# Sheet1.net
KiCad netlist of a schematic drawn in Altium Designer
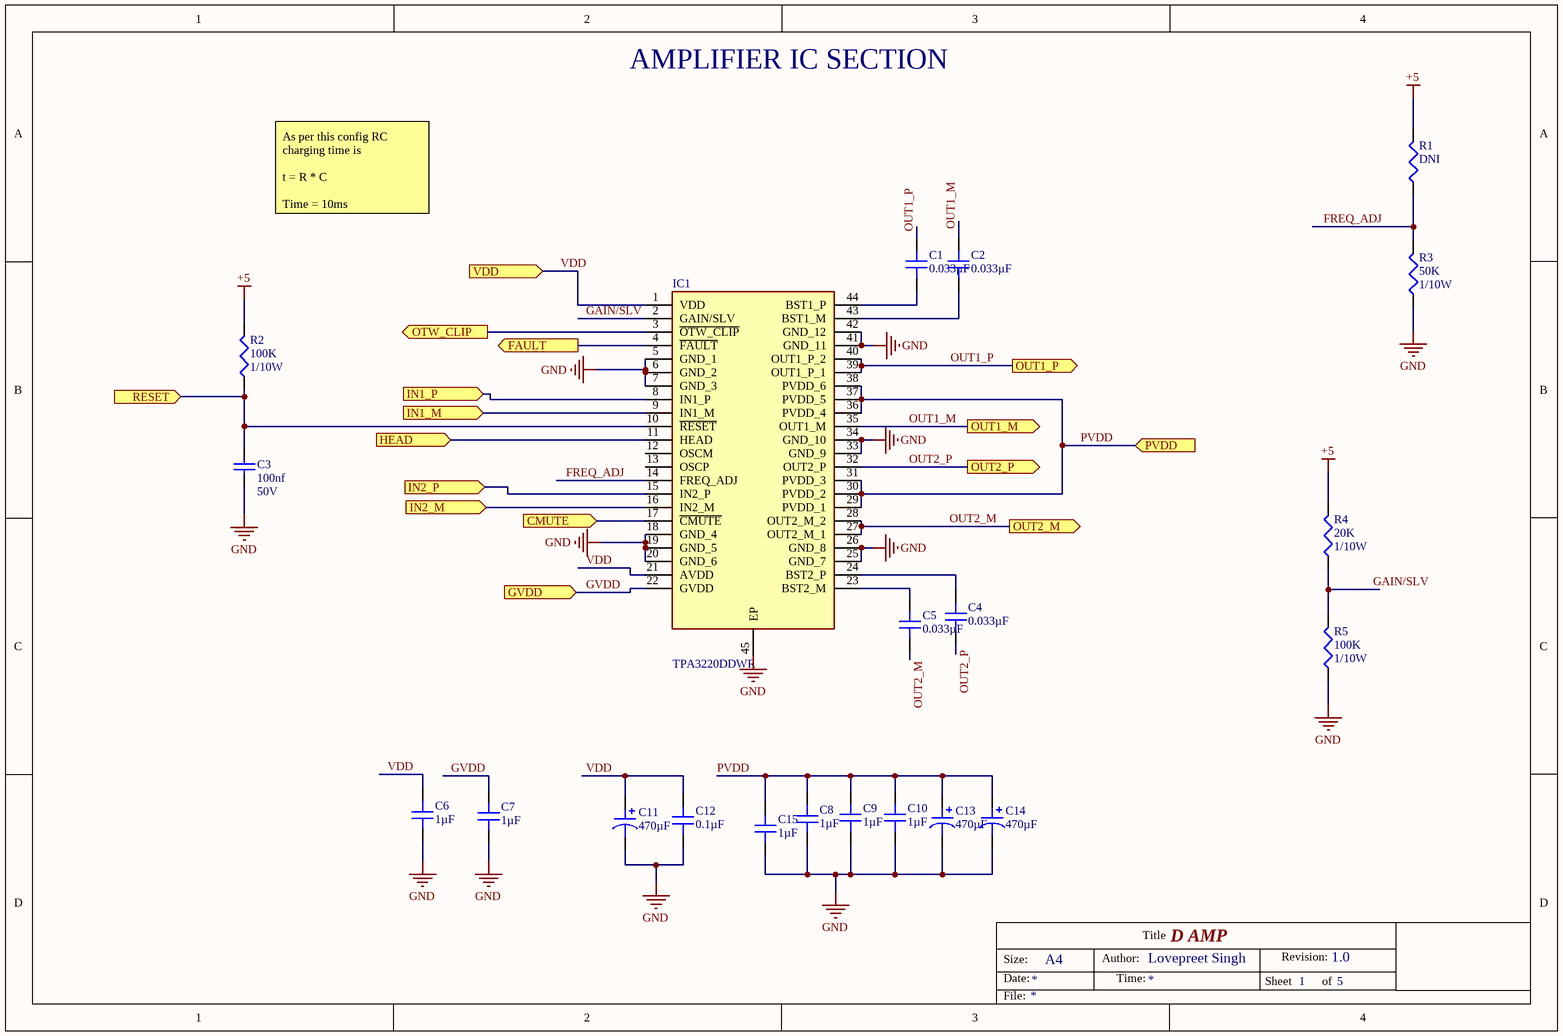
[diagram p0: Sheet1.SchDoc]

(export (version "E")
  (design (tool "Eeschema 10.0.6"))
  (components
    (comp (ref "C1")
      (value "0.033µF")
      (footprint "CAP 0603_1608")
      (description "CAP CER 0.033UF 100V X8R 0603")
      (fields
        (field (name "PART NUMBER") "C1608X8R2A333K080AB")
        (field (name "MANUFACTURER") "TDK Corporation")
      )
      (libsource (lib "Celestial Altium Library - altium_library") (part "Capacitor"))
    )
    (comp (ref "C2")
      (value "0.033µF")
      (footprint "CAP 0603_1608")
      (description "CAP CER 0.033UF 100V X8R 0603")
      (fields
        (field (name "PART NUMBER") "C1608X8R2A333K080AB")
        (field (name "MANUFACTURER") "TDK Corporation")
      )
      (libsource (lib "Celestial Altium Library - altium_library") (part "Capacitor"))
    )
    (comp (ref "C3")
      (value "100nf")
      (footprint "C0603")
      (description "CAP CER 100NF 10% 50V X7R 0603")
      (fields (field (name "VRATING") "50V"))
      (libsource (lib "Database_Libs1") (part "CAP_NPOL"))
    )
    (comp (ref "C4")
      (value "0.033µF")
      (footprint "CAP 0603_1608")
      (description "CAP CER 0.033UF 100V X8R 0603")
      (fields
        (field (name "PART NUMBER") "C1608X8R2A333K080AB")
        (field (name "MANUFACTURER") "TDK Corporation")
      )
      (libsource (lib "Celestial Altium Library - altium_library") (part "Capacitor"))
    )
    (comp (ref "C5")
      (value "0.033µF")
      (footprint "CAP 0603_1608")
      (description "CAP CER 0.033UF 100V X8R 0603")
      (fields
        (field (name "PART NUMBER") "C1608X8R2A333K080AB")
        (field (name "MANUFACTURER") "TDK Corporation")
      )
      (libsource (lib "Celestial Altium Library - altium_library") (part "Capacitor"))
    )
    (comp (ref "C6")
      (value "1µF")
      (footprint "CAP 0805_2012")
      (description "CAP CER 1UF 50V X7R 0805")
      (fields
        (field (name "PART NUMBER") "GCM21BR71H105KA03L")
        (field (name "MANUFACTURER") "Murata Electronics")
      )
      (libsource (lib "Celestial Altium Library - altium_library") (part "Capacitor"))
    )
    (comp (ref "C7")
      (value "1µF")
      (footprint "CAP 0805_2012")
      (description "CAP CER 1UF 50V X7R 0805")
      (fields
        (field (name "PART NUMBER") "GCM21BR71H105KA03L")
        (field (name "MANUFACTURER") "Murata Electronics")
      )
      (libsource (lib "Celestial Altium Library - altium_library") (part "Capacitor"))
    )
    (comp (ref "C8")
      (value "1µF")
      (footprint "CAP 0805_2012")
      (description "CAP CER 1UF 50V X7R 0805")
      (fields
        (field (name "PART NUMBER") "GCM21BR71H105KA03L")
        (field (name "MANUFACTURER") "Murata Electronics")
      )
      (libsource (lib "Celestial Altium Library - altium_library") (part "Capacitor"))
    )
    (comp (ref "C9")
      (value "1µF")
      (footprint "CAP 0805_2012")
      (description "CAP CER 1UF 50V X7R 0805")
      (fields
        (field (name "PART NUMBER") "GCM21BR71H105KA03L")
        (field (name "MANUFACTURER") "Murata Electronics")
      )
      (libsource (lib "Celestial Altium Library - altium_library") (part "Capacitor"))
    )
    (comp (ref "C10")
      (value "1µF")
      (footprint "CAP 0805_2012")
      (description "CAP CER 1UF 50V X7R 0805")
      (fields
        (field (name "PART NUMBER") "GCM21BR71H105KA03L")
        (field (name "MANUFACTURER") "Murata Electronics")
      )
      (libsource (lib "Celestial Altium Library - altium_library") (part "Capacitor"))
    )
    (comp (ref "C11")
      (value "470µF")
      (footprint "CAP TH ALUM ELEC D12.50mm S5.00mm H27.00mm")
      (description "CAP 470UF 50V RAD")
      (fields (field (name "PART NUMBER") "UBT1H471MHD") (field (name "MANUFACTURER") "Nichicon"))
      (libsource (lib "Celestial Altium Library - altium_library") (part "Polarised Capacitor"))
    )
    (comp (ref "C12")
      (value "0.1µF")
      (footprint "CAP 0805_2012")
      (description "CAP CER 0805 10% X8R 50V 100NF")
      (fields (field (name "PART NUMBER") "AC0805KKX8R9BB104") (field (name "MANUFACTURER") "Yageo"))
      (libsource (lib "Celestial Altium Library - altium_library") (part "Capacitor"))
    )
    (comp (ref "C13")
      (value "470µF")
      (footprint "CAP TH ALUM ELEC D12.50mm S5.00mm H27.00mm")
      (description "CAP 470UF 50V RAD")
      (fields (field (name "PART NUMBER") "UBT1H471MHD") (field (name "MANUFACTURER") "Nichicon"))
      (libsource (lib "Celestial Altium Library - altium_library") (part "Polarised Capacitor"))
    )
    (comp (ref "C14")
      (value "470µF")
      (footprint "CAP TH ALUM ELEC D12.50mm S5.00mm H27.00mm")
      (description "CAP 470UF 50V RAD")
      (fields (field (name "PART NUMBER") "UBT1H471MHD") (field (name "MANUFACTURER") "Nichicon"))
      (libsource (lib "Celestial Altium Library - altium_library") (part "Polarised Capacitor"))
    )
    (comp (ref "C15")
      (value "1µF")
      (footprint "CAP 0805_2012")
      (description "CAP CER 1UF 50V X7R 0805")
      (fields
        (field (name "PART NUMBER") "GCM21BR71H105KA03L")
        (field (name "MANUFACTURER") "Murata Electronics")
      )
      (libsource (lib "Celestial Altium Library - altium_library") (part "Capacitor"))
    )
    (comp (ref "IC1")
      (value "TPA3220DDWR")
      (footprint "SamacSys:SOP64P810X120-45N")
      (description "Integrated Circuit")
      (fields (field (name "MOUSER2 PART NUMBER") "595-TPA3220DDWR"))
      (libsource (lib "*") (part "TPA3220DDWR"))
    )
    (comp (ref "R1")
      (value "DNI")
      (footprint "R0603")
      (description "RES SMD 20K 1% 1/10W 0603")
      (libsource (lib "Database_Libs1") (part "RES"))
    )
    (comp (ref "R2")
      (value "100K")
      (footprint "R0603")
      (description "RES SMD 100K 1% 1/10W 0603")
      (fields (field (name "PRATING") "1/10W"))
      (libsource (lib "Database_Libs1") (part "RES"))
    )
    (comp (ref "R3")
      (value "50K")
      (footprint "R0603")
      (description "RES 50K OHM 1% 1/10W 0603")
      (fields (field (name "PRATING") "1/10W"))
      (libsource (lib "Database_Libs1") (part "RES"))
    )
    (comp (ref "R4")
      (value "20K")
      (footprint "R0603")
      (description "RES SMD 20K 1% 1/10W 0603")
      (fields (field (name "PRATING") "1/10W"))
      (libsource (lib "Database_Libs1") (part "RES"))
    )
    (comp (ref "R5")
      (value "100K")
      (footprint "R0603")
      (description "RES SMD 100K 1% 1/10W 0603")
      (fields (field (name "PRATING") "1/10W"))
      (libsource (lib "Database_Libs1") (part "RES"))
    )
  )
  (nets
    (net (code "1") (name "+5") (class "Default")
      (node (ref "R1") (pin "2") (pinfunction "2_2") (pintype "passive"))
      (node (ref "R2") (pin "2") (pinfunction "2_2") (pintype "passive"))
      (node (ref "R4") (pin "2") (pinfunction "2_2") (pintype "passive"))
    )
    (net (code "2") (name "/CMUTE") (class "Default")
      (node (ref "IC1") (pin "17") (pinfunction "~{CMUTE}_17") (pintype "passive"))
    )
    (net (code "3") (name "/FAULT") (class "Default")
      (node (ref "IC1") (pin "4") (pinfunction "~{FAULT}_4") (pintype "passive"))
    )
    (net (code "4") (name "/FREQ_ADJ") (class "Default")
      (node (ref "IC1") (pin "14") (pinfunction "FREQ_ADJ_14") (pintype "passive"))
      (node (ref "R1") (pin "1") (pinfunction "1_1") (pintype "passive"))
      (node (ref "R3") (pin "2") (pinfunction "2_2") (pintype "passive"))
    )
    (net (code "5") (name "/GAIN{slash}SLV") (class "Default")
      (node (ref "IC1") (pin "2") (pinfunction "GAIN/SLV_2") (pintype "passive"))
      (node (ref "R4") (pin "1") (pinfunction "1_1") (pintype "passive"))
      (node (ref "R5") (pin "2") (pinfunction "2_2") (pintype "passive"))
    )
    (net (code "6") (name "/GVDD") (class "Default")
      (node (ref "C7") (pin "2") (pinfunction "2_2") (pintype "passive"))
      (node (ref "IC1") (pin "22") (pinfunction "GVDD_22") (pintype "passive"))
    )
    (net (code "7") (name "/HEAD") (class "Default")
      (node (ref "IC1") (pin "11") (pinfunction "HEAD_11") (pintype "passive"))
    )
    (net (code "8") (name "/IN1_M") (class "Default")
      (node (ref "IC1") (pin "9") (pinfunction "IN1_M_9") (pintype "passive"))
    )
    (net (code "9") (name "/IN1_P") (class "Default")
      (node (ref "IC1") (pin "8") (pinfunction "IN1_P_8") (pintype "passive"))
    )
    (net (code "10") (name "/IN2_M") (class "Default")
      (node (ref "IC1") (pin "16") (pinfunction "IN2_M_16") (pintype "passive"))
    )
    (net (code "11") (name "/IN2_P") (class "Default")
      (node (ref "IC1") (pin "15") (pinfunction "IN2_P_15") (pintype "passive"))
    )
    (net (code "12") (name "/OTW_CLIP") (class "Default")
      (node (ref "IC1") (pin "3") (pinfunction "~{OTW_CLIP}_3") (pintype "passive"))
    )
    (net (code "13") (name "/OUT1_M") (class "Default")
      (node (ref "C2") (pin "2") (pinfunction "2_2") (pintype "passive"))
      (node (ref "IC1") (pin "35") (pinfunction "OUT1_M_35") (pintype "passive"))
    )
    (net (code "14") (name "/OUT1_P") (class "Default")
      (node (ref "C1") (pin "2") (pinfunction "2_2") (pintype "passive"))
      (node (ref "IC1") (pin "39") (pinfunction "OUT1_P_1_39") (pintype "passive"))
      (node (ref "IC1") (pin "40") (pinfunction "OUT1_P_2_40") (pintype "passive"))
    )
    (net (code "15") (name "/OUT2_M") (class "Default")
      (node (ref "C5") (pin "1") (pinfunction "1_1") (pintype "passive"))
      (node (ref "IC1") (pin "27") (pinfunction "OUT2_M_1_27") (pintype "passive"))
      (node (ref "IC1") (pin "28") (pinfunction "OUT2_M_2_28") (pintype "passive"))
    )
    (net (code "16") (name "/OUT2_P") (class "Default")
      (node (ref "C4") (pin "1") (pinfunction "1_1") (pintype "passive"))
      (node (ref "IC1") (pin "32") (pinfunction "OUT2_P_32") (pintype "passive"))
    )
    (net (code "17") (name "/PVDD") (class "Default")
      (node (ref "C10") (pin "2") (pinfunction "2_2") (pintype "passive"))
      (node (ref "C13") (pin "1") (pinfunction "1_1") (pintype "passive"))
      (node (ref "C14") (pin "1") (pinfunction "1_1") (pintype "passive"))
      (node (ref "C15") (pin "2") (pinfunction "2_2") (pintype "passive"))
      (node (ref "C8") (pin "2") (pinfunction "2_2") (pintype "passive"))
      (node (ref "C9") (pin "2") (pinfunction "2_2") (pintype "passive"))
      (node (ref "IC1") (pin "29") (pinfunction "PVDD_1_29") (pintype "passive"))
      (node (ref "IC1") (pin "30") (pinfunction "PVDD_2_30") (pintype "passive"))
      (node (ref "IC1") (pin "31") (pinfunction "PVDD_3_31") (pintype "passive"))
      (node (ref "IC1") (pin "36") (pinfunction "PVDD_4_36") (pintype "passive"))
      (node (ref "IC1") (pin "37") (pinfunction "PVDD_5_37") (pintype "passive"))
      (node (ref "IC1") (pin "38") (pinfunction "PVDD_6_38") (pintype "passive"))
    )
    (net (code "18") (name "/RESET") (class "Default")
      (node (ref "C3") (pin "2") (pinfunction "2_2") (pintype "passive"))
      (node (ref "IC1") (pin "10") (pinfunction "~{RESET}_10") (pintype "passive"))
      (node (ref "R2") (pin "1") (pinfunction "1_1") (pintype "passive"))
    )
    (net (code "19") (name "/VDD") (class "Default")
      (node (ref "C11") (pin "1") (pinfunction "1_1") (pintype "passive"))
      (node (ref "C12") (pin "2") (pinfunction "2_2") (pintype "passive"))
      (node (ref "C6") (pin "2") (pinfunction "2_2") (pintype "passive"))
      (node (ref "IC1") (pin "1") (pinfunction "VDD_1") (pintype "passive"))
      (node (ref "IC1") (pin "21") (pinfunction "AVDD_21") (pintype "passive"))
    )
    (net (code "20") (name "GND") (class "Default")
      (node (ref "C10") (pin "1") (pinfunction "1_1") (pintype "passive"))
      (node (ref "C11") (pin "2") (pinfunction "2_2") (pintype "passive"))
      (node (ref "C12") (pin "1") (pinfunction "1_1") (pintype "passive"))
      (node (ref "C13") (pin "2") (pinfunction "2_2") (pintype "passive"))
      (node (ref "C14") (pin "2") (pinfunction "2_2") (pintype "passive"))
      (node (ref "C15") (pin "1") (pinfunction "1_1") (pintype "passive"))
      (node (ref "C3") (pin "1") (pinfunction "1_1") (pintype "passive"))
      (node (ref "C6") (pin "1") (pinfunction "1_1") (pintype "passive"))
      (node (ref "C7") (pin "1") (pinfunction "1_1") (pintype "passive"))
      (node (ref "C8") (pin "1") (pinfunction "1_1") (pintype "passive"))
      (node (ref "C9") (pin "1") (pinfunction "1_1") (pintype "passive"))
      (node (ref "IC1") (pin "18") (pinfunction "GND_4_18") (pintype "passive"))
      (node (ref "IC1") (pin "19") (pinfunction "GND_5_19") (pintype "passive"))
      (node (ref "IC1") (pin "20") (pinfunction "GND_6_20") (pintype "passive"))
      (node (ref "IC1") (pin "25") (pinfunction "GND_7_25") (pintype "passive"))
      (node (ref "IC1") (pin "26") (pinfunction "GND_8_26") (pintype "passive"))
      (node (ref "IC1") (pin "33") (pinfunction "GND_9_33") (pintype "passive"))
      (node (ref "IC1") (pin "34") (pinfunction "GND_10_34") (pintype "passive"))
      (node (ref "IC1") (pin "41") (pinfunction "GND_11_41") (pintype "passive"))
      (node (ref "IC1") (pin "42") (pinfunction "GND_12_42") (pintype "passive"))
      (node (ref "IC1") (pin "45") (pinfunction "EP_45") (pintype "passive"))
      (node (ref "IC1") (pin "5") (pinfunction "GND_1_5") (pintype "passive"))
      (node (ref "IC1") (pin "6") (pinfunction "GND_2_6") (pintype "passive"))
      (node (ref "IC1") (pin "7") (pinfunction "GND_3_7") (pintype "passive"))
      (node (ref "R3") (pin "1") (pinfunction "1_1") (pintype "passive"))
      (node (ref "R5") (pin "1") (pinfunction "1_1") (pintype "passive"))
    )
    (net (code "21") (name "Net-(IC1-BST1_M)") (class "Default")
      (node (ref "C2") (pin "1") (pinfunction "1_1") (pintype "passive"))
      (node (ref "IC1") (pin "43") (pinfunction "BST1_M_43") (pintype "passive"))
    )
    (net (code "22") (name "Net-(IC1-BST1_P)") (class "Default")
      (node (ref "C1") (pin "1") (pinfunction "1_1") (pintype "passive"))
      (node (ref "IC1") (pin "44") (pinfunction "BST1_P_44") (pintype "passive"))
    )
    (net (code "23") (name "Net-(IC1-BST2_M)") (class "Default")
      (node (ref "C5") (pin "2") (pinfunction "2_2") (pintype "passive"))
      (node (ref "IC1") (pin "23") (pinfunction "BST2_M_23") (pintype "passive"))
    )
    (net (code "24") (name "Net-(IC1-BST2_P)") (class "Default")
      (node (ref "C4") (pin "2") (pinfunction "2_2") (pintype "passive"))
      (node (ref "IC1") (pin "24") (pinfunction "BST2_P_24") (pintype "passive"))
    )
    (net (code "25") (name "unconnected-(IC1-OSCM-Pad12)") (class "Default")
      (node (ref "IC1") (pin "12") (pinfunction "OSCM_12") (pintype "passive"))
    )
    (net (code "26") (name "unconnected-(IC1-OSCP-Pad13)") (class "Default")
      (node (ref "IC1") (pin "13") (pinfunction "OSCP_13") (pintype "passive"))
    )
  )
)
